# PIC.net
KiCad netlist of a schematic drawn in Altium Designer
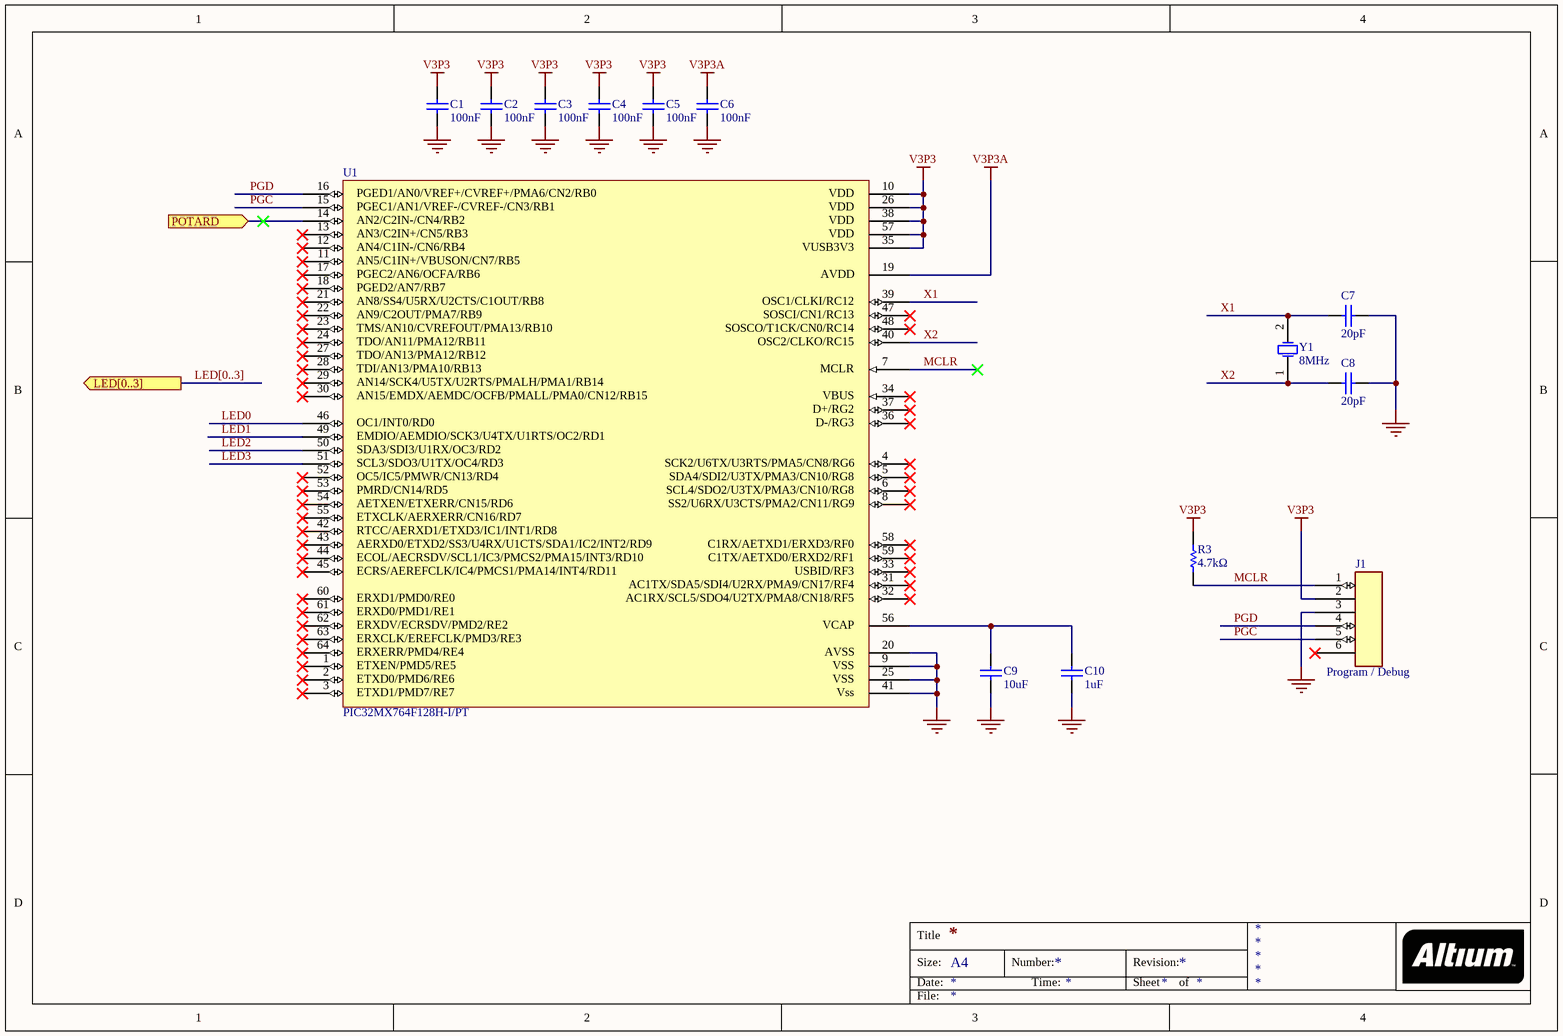
[diagram p0: PIC.SchDoc]

(export (version "E")
  (design (tool "Eeschema 10.0.6"))
  (components
    (comp (ref "C1")
      (value "100nF")
      (footprint "CAPC1608N")
      (description "Capacitor")
      (fields (field (name "PUBLISHER") "Altium Limited"))
      (libsource (lib "Miscellaneous Devices") (part "Cap"))
    )
    (comp (ref "C2")
      (value "100nF")
      (footprint "CAPC1608N")
      (description "Capacitor")
      (fields (field (name "PUBLISHER") "Altium Limited"))
      (libsource (lib "Miscellaneous Devices") (part "Cap"))
    )
    (comp (ref "C3")
      (value "100nF")
      (footprint "CAPC1608N")
      (description "Capacitor")
      (fields (field (name "PUBLISHER") "Altium Limited"))
      (libsource (lib "Miscellaneous Devices") (part "Cap"))
    )
    (comp (ref "C4")
      (value "100nF")
      (footprint "CAPC1608N")
      (description "Capacitor")
      (fields (field (name "PUBLISHER") "Altium Limited"))
      (libsource (lib "Miscellaneous Devices") (part "Cap"))
    )
    (comp (ref "C5")
      (value "100nF")
      (footprint "CAPC1608N")
      (description "Capacitor")
      (fields (field (name "PUBLISHER") "Altium Limited"))
      (libsource (lib "Miscellaneous Devices") (part "Cap"))
    )
    (comp (ref "C6")
      (value "100nF")
      (footprint "CAPC1608N")
      (description "Capacitor")
      (fields (field (name "PUBLISHER") "Altium Limited"))
      (libsource (lib "Miscellaneous Devices") (part "Cap"))
    )
    (comp (ref "C7")
      (value "20pF")
      (footprint "CAPC1608N")
      (description "Capacitor")
      (fields (field (name "PUBLISHER") "Altium Limited"))
      (libsource (lib "Miscellaneous Devices") (part "Cap"))
    )
    (comp (ref "C8")
      (value "20pF")
      (footprint "CAPC1608N")
      (description "Capacitor")
      (fields (field (name "PUBLISHER") "Altium Limited"))
      (libsource (lib "Miscellaneous Devices") (part "Cap"))
    )
    (comp (ref "C9")
      (value "10uF")
      (footprint "CAPC2012N")
      (description "Capacitor")
      (fields (field (name "PUBLISHER") "Altium Limited"))
      (libsource (lib "Miscellaneous Devices") (part "Cap"))
    )
    (comp (ref "C10")
      (value "1uF")
      (footprint "CAPC1608N")
      (description "Capacitor")
      (fields (field (name "PUBLISHER") "Altium Limited"))
      (libsource (lib "Miscellaneous Devices") (part "Cap"))
    )
    (comp (ref "J1") (value "Program / Debug") (footprint "RJ12_90") (libsource (lib "PIC") (part "CON6")))
    (comp (ref "R3")
      (value "4.7kΩ")
      (footprint "RESC1608N")
      (description "Resistor")
      (fields (field (name "PUBLISHER") "Altium Limited"))
      (libsource (lib "Miscellaneous Devices") (part "Res1"))
    )
    (comp (ref "U1")
      (value "PIC32MX764F128H-I/PT")
      (footprint "QFP50P1200X1200X120-64")
      (description "PIC32MX764F128H")
      (libsource (lib "PIC") (part "PIC32MX764F128H-I/PT"))
    )
    (comp (ref "Y1")
      (value "8MHz")
      (footprint "HC49SDLF")
      (description "Crystal Oscillator")
      (fields (field (name "PUBLISHER") "Altium Limited"))
      (libsource (lib "Miscellaneous Devices") (part "XTAL"))
    )
  )
  (nets
    (net (code "1") (name "/LED0") (class "Default")
      (node (ref "U1") (pin "46") (pinfunction "46_46") (pintype "bidirectional"))
    )
    (net (code "2") (name "/LED1") (class "Default")
      (node (ref "U1") (pin "49") (pinfunction "49_49") (pintype "bidirectional"))
    )
    (net (code "3") (name "/LED2") (class "Default")
      (node (ref "U1") (pin "50") (pinfunction "50_50") (pintype "bidirectional"))
    )
    (net (code "4") (name "/LED3") (class "Default")
      (node (ref "U1") (pin "51") (pinfunction "51_51") (pintype "bidirectional"))
    )
    (net (code "6") (name "/MCLR") (class "Default")
      (node (ref "J1") (pin "1") (pinfunction "1_1") (pintype "bidirectional"))
      (node (ref "R3") (pin "1") (pinfunction "1_1") (pintype "passive"))
      (node (ref "U1") (pin "7") (pinfunction "7_7") (pintype "input"))
    )
    (net (code "7") (name "/PGC") (class "Default")
      (node (ref "J1") (pin "5") (pinfunction "5_5") (pintype "bidirectional"))
      (node (ref "U1") (pin "15") (pinfunction "15_15") (pintype "bidirectional"))
    )
    (net (code "8") (name "/PGD") (class "Default")
      (node (ref "J1") (pin "4") (pinfunction "4_4") (pintype "bidirectional"))
      (node (ref "U1") (pin "16") (pinfunction "16_16") (pintype "bidirectional"))
    )
    (net (code "9") (name "/POTARD") (class "Default")
      (node (ref "U1") (pin "14") (pinfunction "14_14") (pintype "bidirectional+no_connect"))
    )
    (net (code "10") (name "/X1") (class "Default")
      (node (ref "C7") (pin "1") (pinfunction "1_1") (pintype "passive"))
      (node (ref "U1") (pin "39") (pinfunction "39_39") (pintype "bidirectional"))
      (node (ref "Y1") (pin "2") (pinfunction "OSC2_2") (pintype "passive"))
    )
    (net (code "11") (name "/X2") (class "Default")
      (node (ref "C8") (pin "1") (pinfunction "1_1") (pintype "passive"))
      (node (ref "U1") (pin "40") (pinfunction "40_40") (pintype "bidirectional"))
      (node (ref "Y1") (pin "1") (pinfunction "OSC1_1") (pintype "passive"))
    )
    (net (code "12") (name "GND") (class "Default")
      (node (ref "C1") (pin "1") (pinfunction "1_1") (pintype "passive"))
      (node (ref "C10") (pin "1") (pinfunction "1_1") (pintype "passive"))
      (node (ref "C2") (pin "1") (pinfunction "1_1") (pintype "passive"))
      (node (ref "C3") (pin "1") (pinfunction "1_1") (pintype "passive"))
      (node (ref "C4") (pin "1") (pinfunction "1_1") (pintype "passive"))
      (node (ref "C5") (pin "1") (pinfunction "1_1") (pintype "passive"))
      (node (ref "C6") (pin "1") (pinfunction "1_1") (pintype "passive"))
      (node (ref "C7") (pin "2") (pinfunction "2_2") (pintype "passive"))
      (node (ref "C8") (pin "2") (pinfunction "2_2") (pintype "passive"))
      (node (ref "C9") (pin "1") (pinfunction "1_1") (pintype "passive"))
      (node (ref "J1") (pin "3") (pinfunction "3_3") (pintype "passive"))
      (node (ref "U1") (pin "20") (pinfunction "20_20") (pintype "passive"))
      (node (ref "U1") (pin "25") (pinfunction "25_25") (pintype "passive"))
      (node (ref "U1") (pin "41") (pinfunction "41_41") (pintype "passive"))
      (node (ref "U1") (pin "9") (pinfunction "9_9") (pintype "passive"))
    )
    (net (code "13") (name "Net-(C10-Pad2)") (class "Default")
      (node (ref "C10") (pin "2") (pinfunction "2_2") (pintype "passive"))
      (node (ref "C9") (pin "2") (pinfunction "2_2") (pintype "passive"))
      (node (ref "U1") (pin "56") (pinfunction "56_56") (pintype "passive"))
    )
    (net (code "14") (name "V3P3") (class "Default")
      (node (ref "C1") (pin "2") (pinfunction "2_2") (pintype "passive"))
      (node (ref "C2") (pin "2") (pinfunction "2_2") (pintype "passive"))
      (node (ref "C3") (pin "2") (pinfunction "2_2") (pintype "passive"))
      (node (ref "C4") (pin "2") (pinfunction "2_2") (pintype "passive"))
      (node (ref "C5") (pin "2") (pinfunction "2_2") (pintype "passive"))
      (node (ref "J1") (pin "2") (pinfunction "2_2") (pintype "power_in"))
      (node (ref "R3") (pin "2") (pinfunction "2_2") (pintype "passive"))
      (node (ref "U1") (pin "10") (pinfunction "10_10") (pintype "power_in"))
      (node (ref "U1") (pin "26") (pinfunction "26_26") (pintype "power_in"))
      (node (ref "U1") (pin "35") (pinfunction "35_35") (pintype "power_in"))
      (node (ref "U1") (pin "38") (pinfunction "38_38") (pintype "power_in"))
      (node (ref "U1") (pin "57") (pinfunction "57_57") (pintype "passive"))
    )
    (net (code "15") (name "V3P3A") (class "Default")
      (node (ref "C6") (pin "2") (pinfunction "2_2") (pintype "passive"))
      (node (ref "U1") (pin "19") (pinfunction "19_19") (pintype "power_in"))
    )
    (net (code "16") (name "unconnected-(J1-Pad6)") (class "Default")
      (node (ref "J1") (pin "6") (pinfunction "6_6") (pintype "passive+no_connect"))
    )
    (net (code "17") (name "unconnected-(U1-Pad1)") (class "Default")
      (node (ref "U1") (pin "1") (pinfunction "1_1") (pintype "bidirectional+no_connect"))
    )
    (net (code "18") (name "unconnected-(U1-Pad2)") (class "Default")
      (node (ref "U1") (pin "2") (pinfunction "2_2") (pintype "bidirectional+no_connect"))
    )
    (net (code "19") (name "unconnected-(U1-Pad3)") (class "Default")
      (node (ref "U1") (pin "3") (pinfunction "3_3") (pintype "bidirectional+no_connect"))
    )
    (net (code "20") (name "unconnected-(U1-Pad4)") (class "Default")
      (node (ref "U1") (pin "4") (pinfunction "4_4") (pintype "bidirectional+no_connect"))
    )
    (net (code "21") (name "unconnected-(U1-Pad5)") (class "Default")
      (node (ref "U1") (pin "5") (pinfunction "5_5") (pintype "bidirectional+no_connect"))
    )
    (net (code "22") (name "unconnected-(U1-Pad6)") (class "Default")
      (node (ref "U1") (pin "6") (pinfunction "6_6") (pintype "bidirectional+no_connect"))
    )
    (net (code "23") (name "unconnected-(U1-Pad8)") (class "Default")
      (node (ref "U1") (pin "8") (pinfunction "8_8") (pintype "bidirectional+no_connect"))
    )
    (net (code "24") (name "unconnected-(U1-Pad11)") (class "Default")
      (node (ref "U1") (pin "11") (pinfunction "11_11") (pintype "bidirectional+no_connect"))
    )
    (net (code "25") (name "unconnected-(U1-Pad12)") (class "Default")
      (node (ref "U1") (pin "12") (pinfunction "12_12") (pintype "bidirectional+no_connect"))
    )
    (net (code "26") (name "unconnected-(U1-Pad13)") (class "Default")
      (node (ref "U1") (pin "13") (pinfunction "13_13") (pintype "bidirectional+no_connect"))
    )
    (net (code "27") (name "unconnected-(U1-Pad17)") (class "Default")
      (node (ref "U1") (pin "17") (pinfunction "17_17") (pintype "bidirectional+no_connect"))
    )
    (net (code "28") (name "unconnected-(U1-Pad18)") (class "Default")
      (node (ref "U1") (pin "18") (pinfunction "18_18") (pintype "bidirectional+no_connect"))
    )
    (net (code "29") (name "unconnected-(U1-Pad21)") (class "Default")
      (node (ref "U1") (pin "21") (pinfunction "21_21") (pintype "bidirectional+no_connect"))
    )
    (net (code "30") (name "unconnected-(U1-Pad22)") (class "Default")
      (node (ref "U1") (pin "22") (pinfunction "22_22") (pintype "bidirectional+no_connect"))
    )
    (net (code "31") (name "unconnected-(U1-Pad23)") (class "Default")
      (node (ref "U1") (pin "23") (pinfunction "23_23") (pintype "bidirectional+no_connect"))
    )
    (net (code "32") (name "unconnected-(U1-Pad24)") (class "Default")
      (node (ref "U1") (pin "24") (pinfunction "24_24") (pintype "bidirectional+no_connect"))
    )
    (net (code "33") (name "unconnected-(U1-Pad27)") (class "Default")
      (node (ref "U1") (pin "27") (pinfunction "27_27") (pintype "bidirectional+no_connect"))
    )
    (net (code "34") (name "unconnected-(U1-Pad28)") (class "Default")
      (node (ref "U1") (pin "28") (pinfunction "28_28") (pintype "bidirectional+no_connect"))
    )
    (net (code "35") (name "unconnected-(U1-Pad29)") (class "Default")
      (node (ref "U1") (pin "29") (pinfunction "29_29") (pintype "bidirectional+no_connect"))
    )
    (net (code "36") (name "unconnected-(U1-Pad30)") (class "Default")
      (node (ref "U1") (pin "30") (pinfunction "30_30") (pintype "bidirectional+no_connect"))
    )
    (net (code "37") (name "unconnected-(U1-Pad31)") (class "Default")
      (node (ref "U1") (pin "31") (pinfunction "31_31") (pintype "bidirectional+no_connect"))
    )
    (net (code "38") (name "unconnected-(U1-Pad32)") (class "Default")
      (node (ref "U1") (pin "32") (pinfunction "32_32") (pintype "bidirectional+no_connect"))
    )
    (net (code "39") (name "unconnected-(U1-Pad33)") (class "Default")
      (node (ref "U1") (pin "33") (pinfunction "33_33") (pintype "bidirectional+no_connect"))
    )
    (net (code "40") (name "unconnected-(U1-Pad34)") (class "Default")
      (node (ref "U1") (pin "34") (pinfunction "34_34") (pintype "input+no_connect"))
    )
    (net (code "41") (name "unconnected-(U1-Pad36)") (class "Default")
      (node (ref "U1") (pin "36") (pinfunction "36_36") (pintype "bidirectional+no_connect"))
    )
    (net (code "42") (name "unconnected-(U1-Pad37)") (class "Default")
      (node (ref "U1") (pin "37") (pinfunction "37_37") (pintype "bidirectional+no_connect"))
    )
    (net (code "43") (name "unconnected-(U1-Pad42)") (class "Default")
      (node (ref "U1") (pin "42") (pinfunction "42_42") (pintype "bidirectional+no_connect"))
    )
    (net (code "44") (name "unconnected-(U1-Pad43)") (class "Default")
      (node (ref "U1") (pin "43") (pinfunction "43_43") (pintype "bidirectional+no_connect"))
    )
    (net (code "45") (name "unconnected-(U1-Pad44)") (class "Default")
      (node (ref "U1") (pin "44") (pinfunction "44_44") (pintype "bidirectional+no_connect"))
    )
    (net (code "46") (name "unconnected-(U1-Pad45)") (class "Default")
      (node (ref "U1") (pin "45") (pinfunction "45_45") (pintype "bidirectional+no_connect"))
    )
    (net (code "47") (name "unconnected-(U1-Pad47)") (class "Default")
      (node (ref "U1") (pin "47") (pinfunction "47_47") (pintype "bidirectional+no_connect"))
    )
    (net (code "48") (name "unconnected-(U1-Pad48)") (class "Default")
      (node (ref "U1") (pin "48") (pinfunction "48_48") (pintype "bidirectional+no_connect"))
    )
    (net (code "49") (name "unconnected-(U1-Pad52)") (class "Default")
      (node (ref "U1") (pin "52") (pinfunction "52_52") (pintype "bidirectional+no_connect"))
    )
    (net (code "50") (name "unconnected-(U1-Pad53)") (class "Default")
      (node (ref "U1") (pin "53") (pinfunction "53_53") (pintype "bidirectional+no_connect"))
    )
    (net (code "51") (name "unconnected-(U1-Pad54)") (class "Default")
      (node (ref "U1") (pin "54") (pinfunction "54_54") (pintype "bidirectional+no_connect"))
    )
    (net (code "52") (name "unconnected-(U1-Pad55)") (class "Default")
      (node (ref "U1") (pin "55") (pinfunction "55_55") (pintype "bidirectional+no_connect"))
    )
    (net (code "53") (name "unconnected-(U1-Pad58)") (class "Default")
      (node (ref "U1") (pin "58") (pinfunction "58_58") (pintype "bidirectional+no_connect"))
    )
    (net (code "54") (name "unconnected-(U1-Pad59)") (class "Default")
      (node (ref "U1") (pin "59") (pinfunction "59_59") (pintype "bidirectional+no_connect"))
    )
    (net (code "55") (name "unconnected-(U1-Pad60)") (class "Default")
      (node (ref "U1") (pin "60") (pinfunction "60_60") (pintype "bidirectional+no_connect"))
    )
    (net (code "56") (name "unconnected-(U1-Pad61)") (class "Default")
      (node (ref "U1") (pin "61") (pinfunction "61_61") (pintype "bidirectional+no_connect"))
    )
    (net (code "57") (name "unconnected-(U1-Pad62)") (class "Default")
      (node (ref "U1") (pin "62") (pinfunction "62_62") (pintype "bidirectional+no_connect"))
    )
    (net (code "58") (name "unconnected-(U1-Pad63)") (class "Default")
      (node (ref "U1") (pin "63") (pinfunction "63_63") (pintype "bidirectional+no_connect"))
    )
    (net (code "59") (name "unconnected-(U1-Pad64)") (class "Default")
      (node (ref "U1") (pin "64") (pinfunction "64_64") (pintype "bidirectional+no_connect"))
    )
  )
)
